# 8_-_SENSORLESS.net
KiCad netlist of a schematic drawn in Altium Designer
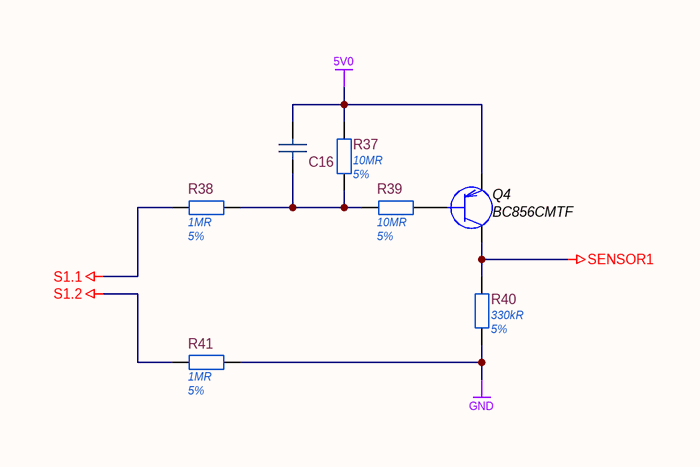
[diagram p0: [8] - SENSORLESS.SchDoc]

(export (version "E")
  (design (tool "Eeschema 10.0.6"))
  (components
    (comp (ref "C16")
      (value "AC0805KRX7R9BB103")
      (footprint "CH0805C")
      (description "CAP CER 10000PF 50V X7R 0805")
      (libsource (lib "Chip Capacitors") (part "AC0805KRX7R9BB103"))
    )
    (comp (ref "Q4")
      (value "BC856CMTF")
      (footprint "SOT Case:SOT23-3")
      (description "TRANS PNP 65V 0.1A SOT-23")
      (fields (field (name "MANUFACTURER") "ON Semiconductor"))
      (libsource (lib "Transistors") (part "BC856CMTF"))
    )
    (comp (ref "R37")
      (value "RC0805JR-0710ML")
      (footprint "CH0805R")
      (description "RES SMD 10M OHM 5% 1/8W 0805")
      (fields (field (name "RESISTANCE") "10MR") (field (name "TOLERANCE") "5%"))
      (libsource (lib "Chip Resistors") (part "RC0805JR-0710ML"))
    )
    (comp (ref "R38")
      (value "RC0805JR-071ML")
      (footprint "CH0805R")
      (description "RES SMD 1M OHM 5% 1/8W 0805")
      (fields (field (name "RESISTANCE") "1MR") (field (name "TOLERANCE") "5%"))
      (libsource (lib "Chip Resistors") (part "RC0805JR-071ML"))
    )
    (comp (ref "R39")
      (value "RC0805JR-0710ML")
      (footprint "CH0805R")
      (description "RES SMD 10M OHM 5% 1/8W 0805")
      (fields (field (name "RESISTANCE") "10MR") (field (name "TOLERANCE") "5%"))
      (libsource (lib "Chip Resistors") (part "RC0805JR-0710ML"))
    )
    (comp (ref "R40")
      (value "RC0805JR-07330KL")
      (footprint "CH0805R")
      (description "RES SMD 330K OHM 5% 1/8W 0805")
      (fields (field (name "RESISTANCE") "330kR") (field (name "TOLERANCE") "5%"))
      (libsource (lib "Chip Resistors") (part "RC0805JR-07330KL"))
    )
    (comp (ref "R41")
      (value "RC0805JR-071ML")
      (footprint "CH0805R")
      (description "RES SMD 1M OHM 5% 1/8W 0805")
      (fields (field (name "RESISTANCE") "1MR") (field (name "TOLERANCE") "5%"))
      (libsource (lib "Chip Resistors") (part "RC0805JR-071ML"))
    )
  )
  (nets
    (net (code "1") (name "5V0") (class "Default")
      (node (ref "C16") (pin "1") (pinfunction "1_1") (pintype "passive"))
      (node (ref "Q4") (pin "2") (pinfunction "B_2") (pintype "passive"))
      (node (ref "R37") (pin "2") (pinfunction "2_2") (pintype "passive"))
    )
    (net (code "2") (name "GND") (class "Default")
      (node (ref "R40") (pin "1") (pinfunction "1_1") (pintype "passive"))
      (node (ref "R41") (pin "2") (pinfunction "2_2") (pintype "passive"))
    )
    (net (code "3") (name "Net-(C16-Pad2)") (class "Default")
      (node (ref "C16") (pin "2") (pinfunction "2_2") (pintype "passive"))
      (node (ref "R37") (pin "1") (pinfunction "1_1") (pintype "passive"))
      (node (ref "R38") (pin "2") (pinfunction "2_2") (pintype "passive"))
      (node (ref "R39") (pin "2") (pinfunction "2_2") (pintype "passive"))
    )
    (net (code "4") (name "Net-(Q4-B-Pad1)") (class "Default")
      (node (ref "Q4") (pin "1") (pinfunction "B_1") (pintype "passive"))
      (node (ref "R39") (pin "1") (pinfunction "1_1") (pintype "passive"))
    )
    (net (code "5") (name "S1.1") (class "Default")
      (node (ref "R38") (pin "1") (pinfunction "1_1") (pintype "passive"))
    )
    (net (code "6") (name "S1.2") (class "Default")
      (node (ref "R41") (pin "1") (pinfunction "1_1") (pintype "passive"))
    )
    (net (code "7") (name "SENSOR1") (class "Default")
      (node (ref "Q4") (pin "3") (pinfunction "B_3") (pintype "passive"))
      (node (ref "R40") (pin "2") (pinfunction "2_2") (pintype "passive"))
    )
  )
)
